# 03_V5_TF_card.net
KiCad netlist of a schematic drawn in Altium Designer
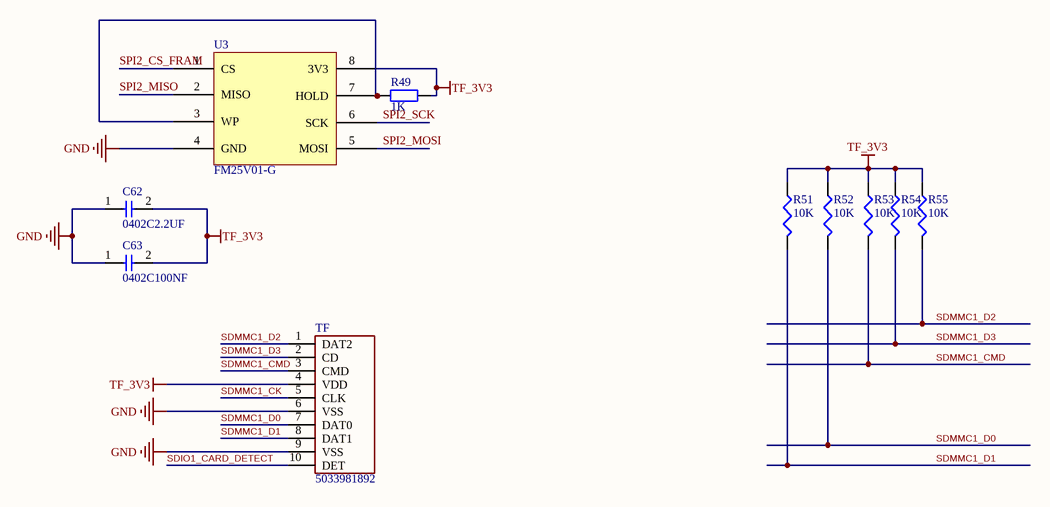
[diagram p0: 03_V5_TF_card.SchDoc]

(export (version "E")
  (design (tool "Eeschema 10.0.6"))
  (components
    (comp (ref "C62") (value "0402C2.2UF") (footprint "0402C") (libsource (lib "CUAV") (part "0402C2.2UF")))
    (comp (ref "C63")
      (value "0402C100NF")
      (footprint "0402C")
      (description "50V 5%")
      (libsource (lib "CUAV") (part "0402C100NF"))
    )
    (comp (ref "R49")
      (value "1K")
      (description "Resistor")
      (fields (field (name "PUBLISHER") "Altium Limited"))
      (libsource (lib "Miscellaneous Devices") (part "Res2"))
    )
    (comp (ref "R51")
      (value "10K")
      (footprint "R0402")
      (libsource (lib "Integrated_Library_RF_FEB_2012") (part "RC0402FR-0749R9L"))
    )
    (comp (ref "R52")
      (value "10K")
      (footprint "R0402")
      (libsource (lib "Integrated_Library_RF_FEB_2012") (part "RC0402FR-0749R9L"))
    )
    (comp (ref "R53")
      (value "10K")
      (footprint "R0402")
      (libsource (lib "Integrated_Library_RF_FEB_2012") (part "RC0402FR-0749R9L"))
    )
    (comp (ref "R54")
      (value "10K")
      (footprint "R0402")
      (libsource (lib "Integrated_Library_RF_FEB_2012") (part "RC0402FR-0749R9L"))
    )
    (comp (ref "R55")
      (value "10K")
      (footprint "R0402")
      (libsource (lib "Integrated_Library_RF_FEB_2012") (part "RC0402FR-0749R9L"))
    )
    (comp (ref "TF")
      (value "5033981892")
      (footprint "5033981892")
      (libsource (lib "CUAV") (part "5033981892"))
    )
    (comp (ref "U3") (value "FM25V01-G") (footprint "SO-8") (libsource (lib "hack") (part "Component_1")))
  )
  (nets
    (net (code "1") (name "/SDIO1_CARD_DETECT") (class "Default")
      (node (ref "TF") (pin "10") (pinfunction "DET_10") (pintype "passive"))
    )
    (net (code "2") (name "/SDMMC1_CK") (class "Default")
      (node (ref "TF") (pin "5") (pinfunction "CLK_5") (pintype "passive"))
    )
    (net (code "3") (name "/SDMMC1_CMD") (class "Default")
      (node (ref "R53") (pin "2") (pinfunction "2_2") (pintype "passive"))
      (node (ref "TF") (pin "3") (pinfunction "CMD_3") (pintype "passive"))
    )
    (net (code "4") (name "/SDMMC1_D0") (class "Default")
      (node (ref "R52") (pin "2") (pinfunction "2_2") (pintype "passive"))
      (node (ref "TF") (pin "7") (pinfunction "DAT0_7") (pintype "passive"))
    )
    (net (code "5") (name "/SDMMC1_D1") (class "Default")
      (node (ref "R51") (pin "2") (pinfunction "2_2") (pintype "passive"))
      (node (ref "TF") (pin "8") (pinfunction "DAT1_8") (pintype "passive"))
    )
    (net (code "6") (name "/SDMMC1_D2") (class "Default")
      (node (ref "R55") (pin "2") (pinfunction "2_2") (pintype "passive"))
      (node (ref "TF") (pin "1") (pinfunction "DAT2_1") (pintype "passive"))
    )
    (net (code "7") (name "/SDMMC1_D3") (class "Default")
      (node (ref "R54") (pin "2") (pinfunction "2_2") (pintype "passive"))
      (node (ref "TF") (pin "2") (pinfunction "CD_2") (pintype "passive"))
    )
    (net (code "8") (name "/SPI2_CS_FRAM") (class "Default")
      (node (ref "U3") (pin "1") (pinfunction "CS_1") (pintype "passive"))
    )
    (net (code "9") (name "/SPI2_MISO") (class "Default")
      (node (ref "U3") (pin "2") (pinfunction "MISO_2") (pintype "passive"))
    )
    (net (code "10") (name "/SPI2_MOSI") (class "Default")
      (node (ref "U3") (pin "5") (pinfunction "MOSI_5") (pintype "passive"))
    )
    (net (code "11") (name "/SPI2_SCK") (class "Default")
      (node (ref "U3") (pin "6") (pinfunction "SCK_6") (pintype "passive"))
    )
    (net (code "12") (name "GND") (class "Default")
      (node (ref "C62") (pin "1") (pintype "passive"))
      (node (ref "C63") (pin "1") (pintype "passive"))
      (node (ref "TF") (pin "6") (pinfunction "VSS_6") (pintype "passive"))
      (node (ref "TF") (pin "9") (pinfunction "VSS_9") (pintype "passive"))
      (node (ref "U3") (pin "4") (pinfunction "GND_4") (pintype "passive"))
    )
    (net (code "13") (name "Net-(U3-HOLD)") (class "Default")
      (node (ref "R49") (pin "2") (pinfunction "2_2") (pintype "passive"))
      (node (ref "U3") (pin "3") (pinfunction "WP_3") (pintype "passive"))
      (node (ref "U3") (pin "7") (pinfunction "HOLD_7") (pintype "passive"))
    )
    (net (code "14") (name "TF_3V3") (class "Default")
      (node (ref "C62") (pin "2") (pintype "passive"))
      (node (ref "C63") (pin "2") (pintype "passive"))
      (node (ref "R49") (pin "1") (pinfunction "1_1") (pintype "passive"))
      (node (ref "R51") (pin "1") (pinfunction "1_1") (pintype "passive"))
      (node (ref "R52") (pin "1") (pinfunction "1_1") (pintype "passive"))
      (node (ref "R53") (pin "1") (pinfunction "1_1") (pintype "passive"))
      (node (ref "R54") (pin "1") (pinfunction "1_1") (pintype "passive"))
      (node (ref "R55") (pin "1") (pinfunction "1_1") (pintype "passive"))
      (node (ref "TF") (pin "4") (pinfunction "VDD_4") (pintype "passive"))
      (node (ref "U3") (pin "8") (pinfunction "3V3_8") (pintype "passive"))
    )
  )
)
